# SW6208_A_A_B_C_L_MCU_188.net
KiCad netlist of a schematic drawn in Altium Designer
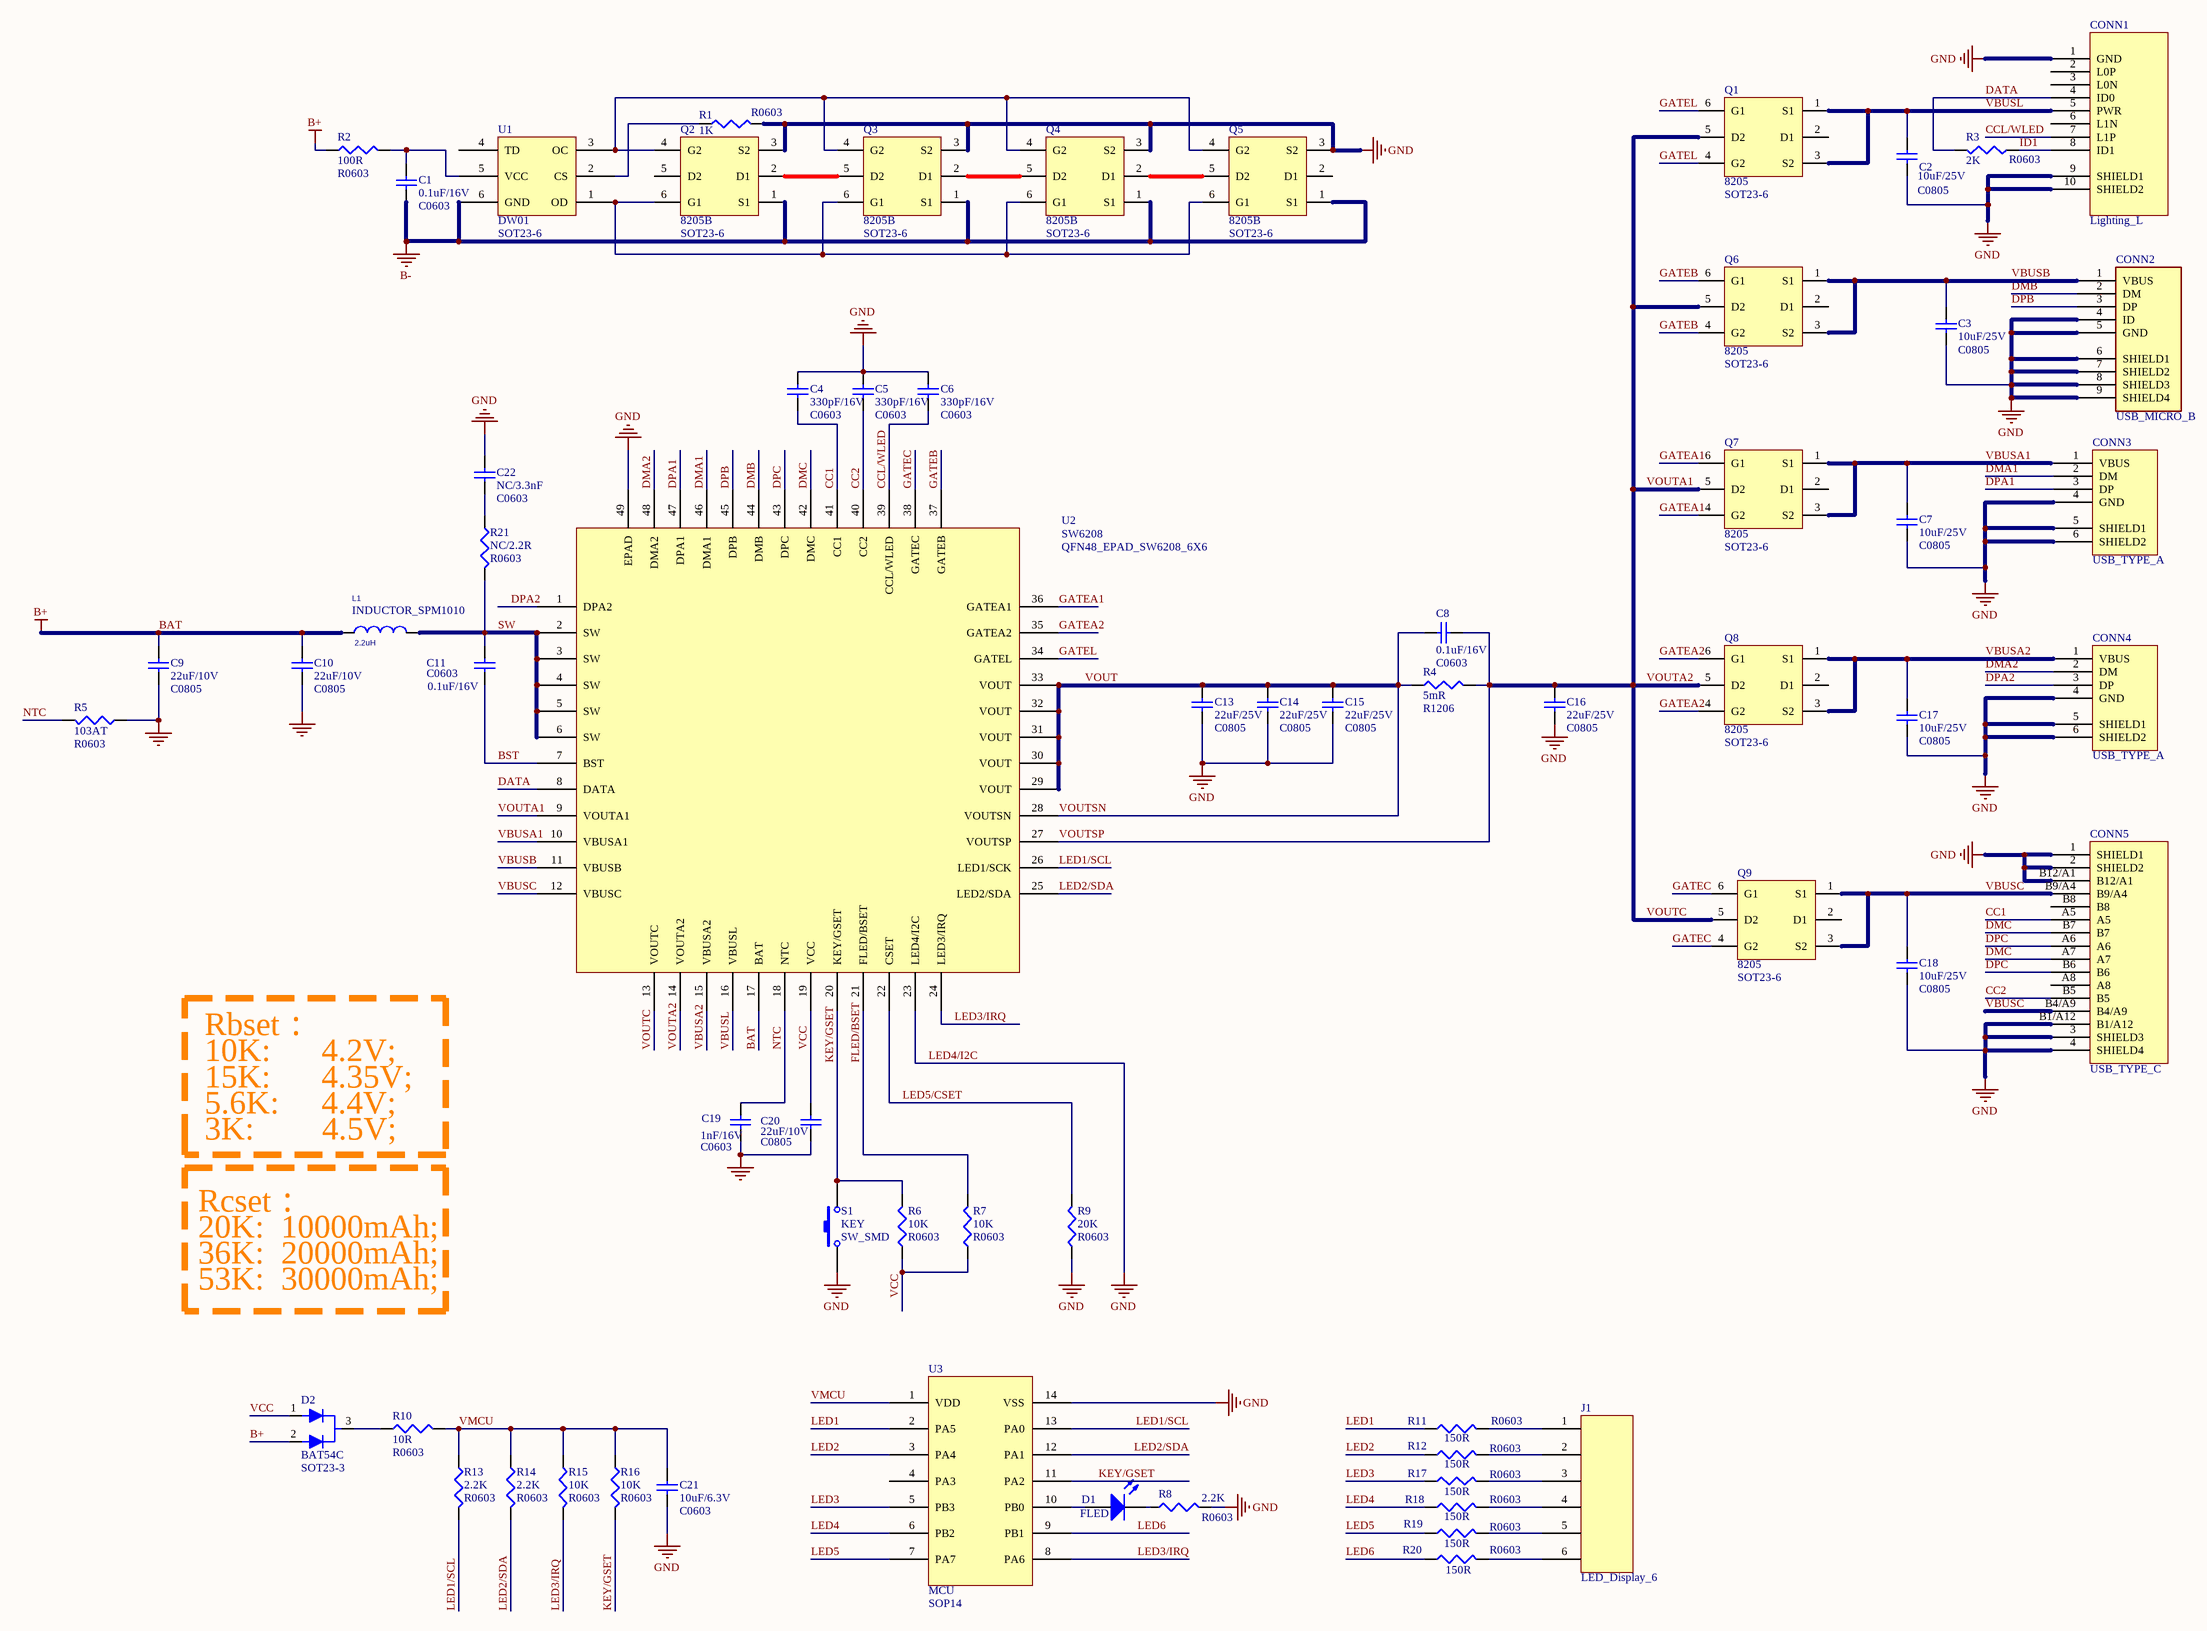
[diagram p0: SW6208+A+A+B+C+L+MCU+普通188数码管.SchDoc]

(export (version "E")
  (design (tool "Eeschema 10.0.6"))
  (components
    (comp (ref "C1")
      (value "0.1uF/16V")
      (footprint "C0603")
      (description "Capacitor")
      (fields (field (name "PUBLISHER") "Altium Limited"))
      (libsource (lib "参考设计器件原理图更新") (part "CAP0603"))
    )
    (comp (ref "C2")
      (value "10uF/25V")
      (footprint "C0805")
      (description "Capacitor")
      (fields (field (name "PUBLISHER") "Altium Limited"))
      (libsource (lib "参考设计器件原理图更新") (part "CAP0805"))
    )
    (comp (ref "C3")
      (value "10uF/25V")
      (footprint "C0805")
      (description "Capacitor")
      (fields (field (name "PUBLISHER") "Altium Limited"))
      (libsource (lib "参考设计器件原理图更新") (part "CAP0805"))
    )
    (comp (ref "C4")
      (value "330pF/16V")
      (footprint "C0603")
      (description "Capacitor")
      (fields (field (name "PUBLISHER") "Altium Limited"))
      (libsource (lib "参考设计器件原理图更新") (part "CAP0603"))
    )
    (comp (ref "C5")
      (value "330pF/16V")
      (footprint "C0603")
      (description "Capacitor")
      (fields (field (name "PUBLISHER") "Altium Limited"))
      (libsource (lib "参考设计器件原理图更新") (part "CAP0603"))
    )
    (comp (ref "C6")
      (value "330pF/16V")
      (footprint "C0603")
      (description "Capacitor")
      (fields (field (name "PUBLISHER") "Altium Limited"))
      (libsource (lib "参考设计器件原理图更新") (part "CAP0603"))
    )
    (comp (ref "C7")
      (value "10uF/25V")
      (footprint "C0805")
      (description "Capacitor")
      (fields (field (name "PUBLISHER") "Altium Limited"))
      (libsource (lib "参考设计器件原理图更新") (part "CAP0805"))
    )
    (comp (ref "C8")
      (value "0.1uF/16V")
      (footprint "C0603")
      (description "Capacitor")
      (fields (field (name "PUBLISHER") "Altium Limited"))
      (libsource (lib "参考设计器件原理图更新") (part "CAP0603"))
    )
    (comp (ref "C9")
      (value "22uF/10V")
      (footprint "C0805")
      (description "Capacitor")
      (fields (field (name "PUBLISHER") "Altium Limited"))
      (libsource (lib "参考设计器件原理图更新") (part "CAP0805"))
    )
    (comp (ref "C10")
      (value "22uF/10V")
      (footprint "C0805")
      (description "Capacitor")
      (fields (field (name "PUBLISHER") "Altium Limited"))
      (libsource (lib "参考设计器件原理图更新") (part "CAP0805"))
    )
    (comp (ref "C11")
      (value "0.1uF/16V")
      (footprint "C0603")
      (description "Capacitor")
      (fields (field (name "PUBLISHER") "Altium Limited"))
      (libsource (lib "参考设计器件原理图更新") (part "CAP0603"))
    )
    (comp (ref "C13")
      (value "22uF/25V")
      (footprint "C0805")
      (description "Capacitor")
      (fields (field (name "PUBLISHER") "Altium Limited"))
      (libsource (lib "参考设计器件原理图更新") (part "CAP0805"))
    )
    (comp (ref "C14")
      (value "22uF/25V")
      (footprint "C0805")
      (description "Capacitor")
      (fields (field (name "PUBLISHER") "Altium Limited"))
      (libsource (lib "参考设计器件原理图更新") (part "CAP0805"))
    )
    (comp (ref "C15")
      (value "22uF/25V")
      (footprint "C0805")
      (description "Capacitor")
      (fields (field (name "PUBLISHER") "Altium Limited"))
      (libsource (lib "参考设计器件原理图更新") (part "CAP0805"))
    )
    (comp (ref "C16")
      (value "22uF/25V")
      (footprint "C0805")
      (description "Capacitor")
      (fields (field (name "PUBLISHER") "Altium Limited"))
      (libsource (lib "参考设计器件原理图更新") (part "CAP0805"))
    )
    (comp (ref "C17")
      (value "10uF/25V")
      (footprint "C0805")
      (description "Capacitor")
      (fields (field (name "PUBLISHER") "Altium Limited"))
      (libsource (lib "参考设计器件原理图更新") (part "CAP0805"))
    )
    (comp (ref "C18")
      (value "10uF/25V")
      (footprint "C0805")
      (description "Capacitor")
      (fields (field (name "PUBLISHER") "Altium Limited"))
      (libsource (lib "参考设计器件原理图更新") (part "CAP0805"))
    )
    (comp (ref "C19")
      (value "1nF/16V")
      (footprint "C0603")
      (description "Capacitor")
      (fields (field (name "PUBLISHER") "Altium Limited"))
      (libsource (lib "参考设计器件原理图更新") (part "CAP0603"))
    )
    (comp (ref "C20")
      (value "22uF/10V")
      (footprint "C0805")
      (description "Capacitor")
      (fields (field (name "PUBLISHER") "Altium Limited"))
      (libsource (lib "参考设计器件原理图更新") (part "CAP0805"))
    )
    (comp (ref "C21")
      (value "10uF/6.3V")
      (footprint "C0603")
      (description "Capacitor")
      (fields (field (name "PUBLISHER") "Altium Limited"))
      (libsource (lib "参考设计器件原理图更新") (part "CAP0603"))
    )
    (comp (ref "C22")
      (value "NC/3.3nF")
      (footprint "C0603")
      (description "Capacitor")
      (fields (field (name "PUBLISHER") "Altium Limited"))
      (libsource (lib "参考设计器件原理图更新") (part "CAP0603"))
    )
    (comp (ref "CONN1")
      (value "Lighting_L")
      (footprint "Lighting")
      (libsource (lib "参考设计器件原理图更新") (part "LIGHTING_PORT"))
    )
    (comp (ref "CONN2")
      (value "USB_MICRO_B")
      (footprint "USB_MICRO_B")
      (libsource (lib "参考设计器件原理图更新") (part "USB_MICRO_B"))
    )
    (comp (ref "CONN3")
      (value "USB_TYPE_A")
      (footprint "USB_TYPE_A")
      (libsource (lib "参考设计器件原理图更新") (part "USB_TYPE_A"))
    )
    (comp (ref "CONN4")
      (value "USB_TYPE_A")
      (footprint "USB_TYPE_A")
      (libsource (lib "参考设计器件原理图更新") (part "USB_TYPE_A"))
    )
    (comp (ref "CONN5")
      (value "USB_TYPE_C")
      (footprint "LOUISAD:USB_TYPE_C")
      (libsource (lib "参考设计器件原理图更新") (part "USB_TYPE_C"))
    )
    (comp (ref "D1")
      (value "FLED")
      (footprint "LED0603")
      (description "LED")
      (fields (field (name "PUBLISHER") "Altium Limited"))
      (libsource (lib "参考设计器件原理图更新") (part "LED_0603"))
    )
    (comp (ref "D2")
      (value "BAT54C")
      (footprint "SOT23-3")
      (description "Diode")
      (libsource (lib "参考设计器件原理图更新") (part "BAT54C"))
    )
    (comp (ref "J1")
      (value "LED_Display_6")
      (footprint "SEG-6")
      (description "188_LED_Display")
      (libsource (lib "参考设计器件原理图更新") (part "LED_Display_6"))
    )
    (comp (ref "L1")
      (value "2.2uH")
      (footprint "INDUCTOR_SPM1010")
      (description "INDUCTOR")
      (libsource (lib "参考设计器件原理图更新") (part "INDUCTOR_SPM1010"))
    )
    (comp (ref "Q1")
      (value "8205")
      (footprint "SOT23-6")
      (description "NMOS")
      (fields (field (name "FOOTPRINF") "SOT23-6"))
      (libsource (lib "参考设计器件原理图更新") (part "8205"))
    )
    (comp (ref "Q2")
      (value "8205B")
      (footprint "SOT23-6")
      (description "NMOS")
      (fields (field (name "FOOTPRINF") "SOT23-6"))
      (libsource (lib "") (part "8205_1"))
    )
    (comp (ref "Q3")
      (value "8205B")
      (footprint "SOT23-6")
      (description "NMOS")
      (fields (field (name "FOOTPRINF") "SOT23-6"))
      (libsource (lib "") (part "8205_1"))
    )
    (comp (ref "Q4")
      (value "8205B")
      (footprint "SOT23-6")
      (description "NMOS")
      (fields (field (name "FOOTPRINF") "SOT23-6"))
      (libsource (lib "") (part "8205_1"))
    )
    (comp (ref "Q5")
      (value "8205B")
      (footprint "SOT23-6")
      (description "NMOS")
      (fields (field (name "FOOTPRINF") "SOT23-6"))
      (libsource (lib "") (part "8205_1"))
    )
    (comp (ref "Q6")
      (value "8205")
      (footprint "SOT23-6")
      (description "NMOS")
      (fields (field (name "FOOTPRINF") "SOT23-6"))
      (libsource (lib "参考设计器件原理图更新") (part "8205"))
    )
    (comp (ref "Q7")
      (value "8205")
      (footprint "SOT23-6")
      (description "NMOS")
      (fields (field (name "FOOTPRINF") "SOT23-6"))
      (libsource (lib "参考设计器件原理图更新") (part "8205"))
    )
    (comp (ref "Q8")
      (value "8205")
      (footprint "SOT23-6")
      (description "NMOS")
      (fields (field (name "FOOTPRINF") "SOT23-6"))
      (libsource (lib "参考设计器件原理图更新") (part "8205"))
    )
    (comp (ref "Q9")
      (value "8205")
      (footprint "SOT23-6")
      (description "NMOS")
      (fields (field (name "FOOTPRINF") "SOT23-6"))
      (libsource (lib "参考设计器件原理图更新") (part "8205"))
    )
    (comp (ref "R1")
      (value "1K")
      (footprint "R0603")
      (description "Resistor")
      (fields (field (name "PUBLISHER") "Altium Limited"))
      (libsource (lib "参考设计器件原理图更新") (part "RES_0603"))
    )
    (comp (ref "R2")
      (value "100R")
      (footprint "R0603")
      (description "Resistor")
      (fields (field (name "PUBLISHER") "Altium Limited"))
      (libsource (lib "参考设计器件原理图更新") (part "RES_0603"))
    )
    (comp (ref "R3")
      (value "2K")
      (footprint "R0603")
      (description "Resistor")
      (fields (field (name "PUBLISHER") "Altium Limited"))
      (libsource (lib "参考设计器件原理图更新") (part "RES_0603"))
    )
    (comp (ref "R4")
      (value "5mR")
      (footprint "R1206")
      (description "Resistor")
      (fields (field (name "PUBLISHER") "Altium Limited"))
      (libsource (lib "参考设计器件原理图更新") (part "RES_1206"))
    )
    (comp (ref "R5")
      (value "103AT")
      (footprint "R0603")
      (description "Resistor")
      (fields (field (name "PUBLISHER") "Altium Limited"))
      (libsource (lib "参考设计器件原理图更新") (part "RES_0603"))
    )
    (comp (ref "R6")
      (value "10K")
      (footprint "R0603")
      (description "Resistor")
      (fields (field (name "PUBLISHER") "Altium Limited"))
      (libsource (lib "参考设计器件原理图更新") (part "RES_0603"))
    )
    (comp (ref "R7")
      (value "10K")
      (footprint "R0603")
      (description "Resistor")
      (fields (field (name "PUBLISHER") "Altium Limited"))
      (libsource (lib "参考设计器件原理图更新") (part "RES_0603"))
    )
    (comp (ref "R8")
      (value "2.2K")
      (footprint "R0603")
      (description "Resistor")
      (fields (field (name "PUBLISHER") "Altium Limited"))
      (libsource (lib "参考设计器件原理图更新") (part "RES_0603"))
    )
    (comp (ref "R9")
      (value "20K")
      (footprint "R0603")
      (description "Resistor")
      (fields (field (name "PUBLISHER") "Altium Limited"))
      (libsource (lib "参考设计器件原理图更新") (part "RES_0603"))
    )
    (comp (ref "R10")
      (value "10R")
      (footprint "R0603")
      (description "Resistor")
      (fields (field (name "PUBLISHER") "Altium Limited"))
      (libsource (lib "参考设计器件原理图更新") (part "RES_0603"))
    )
    (comp (ref "R11")
      (value "150R")
      (footprint "R0603")
      (description "Resistor")
      (fields (field (name "PUBLISHER") "Altium Limited"))
      (libsource (lib "参考设计器件原理图更新") (part "RES_0603"))
    )
    (comp (ref "R12")
      (value "150R")
      (footprint "R0603")
      (description "Resistor")
      (fields (field (name "PUBLISHER") "Altium Limited"))
      (libsource (lib "参考设计器件原理图更新") (part "RES_0603"))
    )
    (comp (ref "R13")
      (value "2.2K")
      (footprint "R0603")
      (description "Resistor")
      (fields (field (name "PUBLISHER") "Altium Limited"))
      (libsource (lib "参考设计器件原理图更新") (part "RES_0603"))
    )
    (comp (ref "R14")
      (value "2.2K")
      (footprint "R0603")
      (description "Resistor")
      (fields (field (name "PUBLISHER") "Altium Limited"))
      (libsource (lib "参考设计器件原理图更新") (part "RES_0603"))
    )
    (comp (ref "R15")
      (value "10K")
      (footprint "R0603")
      (description "Resistor")
      (fields (field (name "PUBLISHER") "Altium Limited"))
      (libsource (lib "参考设计器件原理图更新") (part "RES_0603"))
    )
    (comp (ref "R16")
      (value "10K")
      (footprint "R0603")
      (description "Resistor")
      (fields (field (name "PUBLISHER") "Altium Limited"))
      (libsource (lib "参考设计器件原理图更新") (part "RES_0603"))
    )
    (comp (ref "R17")
      (value "150R")
      (footprint "R0603")
      (description "Resistor")
      (fields (field (name "PUBLISHER") "Altium Limited"))
      (libsource (lib "参考设计器件原理图更新") (part "RES_0603"))
    )
    (comp (ref "R18")
      (value "150R")
      (footprint "R0603")
      (description "Resistor")
      (fields (field (name "PUBLISHER") "Altium Limited"))
      (libsource (lib "参考设计器件原理图更新") (part "RES_0603"))
    )
    (comp (ref "R19")
      (value "150R")
      (footprint "R0603")
      (description "Resistor")
      (fields (field (name "PUBLISHER") "Altium Limited"))
      (libsource (lib "参考设计器件原理图更新") (part "RES_0603"))
    )
    (comp (ref "R20")
      (value "150R")
      (footprint "R0603")
      (description "Resistor")
      (fields (field (name "PUBLISHER") "Altium Limited"))
      (libsource (lib "参考设计器件原理图更新") (part "RES_0603"))
    )
    (comp (ref "R21")
      (value "NC/2.2R")
      (footprint "R0603")
      (description "Resistor")
      (fields (field (name "PUBLISHER") "Altium Limited"))
      (libsource (lib "参考设计器件原理图更新") (part "RES_0603"))
    )
    (comp (ref "S1")
      (value "KEY")
      (footprint "SW_SMD")
      (fields (field (name "FOOTPRINF") "SW_SMD"))
      (libsource (lib "参考设计器件原理图更新") (part "SW K"))
    )
    (comp (ref "U1")
      (value "DW01")
      (footprint "SOT23-6")
      (description "BAT_PROTECT_IC")
      (libsource (lib "参考设计器件原理图更新") (part "DW01"))
    )
    (comp (ref "U2")
      (value "SW6208")
      (footprint "QFN48_EPAD_SW6208_6X6")
      (description "IC")
      (libsource (lib "芯片型号原理图") (part "SW6208"))
    )
    (comp (ref "U3")
      (value "MCU")
      (footprint "SOP14")
      (description "IC")
      (libsource (lib "参考设计器件原理图更新") (part "MCU_SOP14"))
    )
  )
  (nets
    (net (code "1") (name "/BST") (class "Default")
      (node (ref "C11") (pin "1") (pinfunction "1_1") (pintype "passive"))
      (node (ref "U2") (pin "7") (pinfunction "BST_7") (pintype "passive"))
    )
    (net (code "2") (name "/CC1") (class "Default")
      (node (ref "C4") (pin "1") (pinfunction "1_1") (pintype "passive"))
      (node (ref "CONN5") (pin "A5") (pinfunction "A5_A5") (pintype "passive"))
      (node (ref "U2") (pin "41") (pinfunction "CC1_41") (pintype "passive"))
    )
    (net (code "3") (name "/CC2") (class "Default")
      (node (ref "C5") (pin "1") (pinfunction "1_1") (pintype "passive"))
      (node (ref "CONN5") (pin "B5") (pinfunction "B5_B5") (pintype "passive"))
      (node (ref "U2") (pin "40") (pinfunction "CC2_40") (pintype "passive"))
    )
    (net (code "4") (name "/CCL{slash}WLED") (class "Default")
      (node (ref "C6") (pin "1") (pinfunction "1_1") (pintype "passive"))
      (node (ref "CONN1") (pin "7") (pinfunction "L1P_7") (pintype "passive"))
      (node (ref "U2") (pin "39") (pinfunction "CCL/WLED_39") (pintype "passive"))
    )
    (net (code "5") (name "/DATA") (class "Default")
      (node (ref "CONN1") (pin "4") (pinfunction "ID0_4") (pintype "passive"))
      (node (ref "R3") (pin "2") (pinfunction "2_2") (pintype "passive"))
      (node (ref "U2") (pin "8") (pinfunction "DATA_8") (pintype "passive"))
    )
    (net (code "6") (name "/DMA1") (class "Default")
      (node (ref "CONN3") (pin "2") (pinfunction "DM_2") (pintype "passive"))
      (node (ref "U2") (pin "46") (pinfunction "DMA1_46") (pintype "passive"))
    )
    (net (code "7") (name "/DMA2") (class "Default")
      (node (ref "CONN4") (pin "2") (pinfunction "DM_2") (pintype "passive"))
      (node (ref "U2") (pin "48") (pinfunction "DMA2_48") (pintype "passive"))
    )
    (net (code "8") (name "/DMB") (class "Default")
      (node (ref "CONN2") (pin "2") (pinfunction "DM_2") (pintype "passive"))
      (node (ref "U2") (pin "44") (pinfunction "DMB_44") (pintype "passive"))
    )
    (net (code "9") (name "/DMC") (class "Default")
      (node (ref "CONN5") (pin "A7") (pinfunction "A7_A7") (pintype "passive"))
      (node (ref "CONN5") (pin "B7") (pinfunction "B7_B7") (pintype "passive"))
      (node (ref "U2") (pin "42") (pinfunction "DMC_42") (pintype "passive"))
    )
    (net (code "10") (name "/DPA1") (class "Default")
      (node (ref "CONN3") (pin "3") (pinfunction "DP_3") (pintype "passive"))
      (node (ref "U2") (pin "47") (pinfunction "DPA1_47") (pintype "passive"))
    )
    (net (code "11") (name "/DPA2") (class "Default")
      (node (ref "CONN4") (pin "3") (pinfunction "DP_3") (pintype "passive"))
      (node (ref "U2") (pin "1") (pinfunction "DPA2_1") (pintype "passive"))
    )
    (net (code "12") (name "/DPB") (class "Default")
      (node (ref "CONN2") (pin "3") (pinfunction "DP_3") (pintype "passive"))
      (node (ref "U2") (pin "45") (pinfunction "DPB_45") (pintype "passive"))
    )
    (net (code "13") (name "/DPC") (class "Default")
      (node (ref "CONN5") (pin "A6") (pinfunction "A6_A6") (pintype "passive"))
      (node (ref "CONN5") (pin "B6") (pinfunction "B6_B6") (pintype "passive"))
      (node (ref "U2") (pin "43") (pinfunction "DPC_43") (pintype "passive"))
    )
    (net (code "14") (name "/FLED{slash}BSET") (class "Default")
      (node (ref "R7") (pin "2") (pinfunction "2_2") (pintype "passive"))
      (node (ref "U2") (pin "21") (pinfunction "FLED/BSET_21") (pintype "passive"))
    )
    (net (code "15") (name "/GATEA1") (class "Default")
      (node (ref "Q7") (pin "4") (pinfunction "G2_4") (pintype "passive"))
      (node (ref "Q7") (pin "6") (pinfunction "G1_6") (pintype "passive"))
      (node (ref "U2") (pin "36") (pinfunction "GATEA1_36") (pintype "passive"))
    )
    (net (code "16") (name "/GATEA2") (class "Default")
      (node (ref "Q8") (pin "4") (pinfunction "G2_4") (pintype "passive"))
      (node (ref "Q8") (pin "6") (pinfunction "G1_6") (pintype "passive"))
      (node (ref "U2") (pin "35") (pinfunction "GATEA2_35") (pintype "passive"))
    )
    (net (code "17") (name "/GATEB") (class "Default")
      (node (ref "Q6") (pin "4") (pinfunction "G2_4") (pintype "passive"))
      (node (ref "Q6") (pin "6") (pinfunction "G1_6") (pintype "passive"))
      (node (ref "U2") (pin "37") (pinfunction "GATEB_37") (pintype "passive"))
    )
    (net (code "18") (name "/GATEC") (class "Default")
      (node (ref "Q9") (pin "4") (pinfunction "G2_4") (pintype "passive"))
      (node (ref "Q9") (pin "6") (pinfunction "G1_6") (pintype "passive"))
      (node (ref "U2") (pin "38") (pinfunction "GATEC_38") (pintype "passive"))
    )
    (net (code "19") (name "/GATEL") (class "Default")
      (node (ref "Q1") (pin "4") (pinfunction "G2_4") (pintype "passive"))
      (node (ref "Q1") (pin "6") (pinfunction "G1_6") (pintype "passive"))
      (node (ref "U2") (pin "34") (pinfunction "GATEL_34") (pintype "passive"))
    )
    (net (code "20") (name "/ID1") (class "Default")
      (node (ref "CONN1") (pin "8") (pinfunction "ID1_8") (pintype "passive"))
      (node (ref "R3") (pin "1") (pinfunction "1_1") (pintype "passive"))
    )
    (net (code "21") (name "/KEY{slash}GSET") (class "Default")
      (node (ref "R16") (pin "2") (pinfunction "2_2") (pintype "passive"))
      (node (ref "R6") (pin "2") (pinfunction "2_2") (pintype "passive"))
      (node (ref "S1") (pin "2") (pinfunction "2_2") (pintype "passive"))
      (node (ref "U2") (pin "20") (pinfunction "KEY/GSET_20") (pintype "passive"))
      (node (ref "U3") (pin "11") (pinfunction "PA2_11") (pintype "passive"))
    )
    (net (code "22") (name "/LED1") (class "Default")
      (node (ref "R11") (pin "1") (pinfunction "1_1") (pintype "passive"))
      (node (ref "U3") (pin "2") (pinfunction "PA5_2") (pintype "passive"))
    )
    (net (code "23") (name "/LED1{slash}SCL") (class "Default")
      (node (ref "R13") (pin "2") (pinfunction "2_2") (pintype "passive"))
      (node (ref "U2") (pin "26") (pinfunction "LED1/SCK_26") (pintype "passive"))
      (node (ref "U3") (pin "13") (pinfunction "PA0_13") (pintype "passive"))
    )
    (net (code "24") (name "/LED2") (class "Default")
      (node (ref "R12") (pin "1") (pinfunction "1_1") (pintype "passive"))
      (node (ref "U3") (pin "3") (pinfunction "PA4_3") (pintype "passive"))
    )
    (net (code "25") (name "/LED2{slash}SDA") (class "Default")
      (node (ref "R14") (pin "2") (pinfunction "2_2") (pintype "passive"))
      (node (ref "U2") (pin "25") (pinfunction "LED2/SDA_25") (pintype "passive"))
      (node (ref "U3") (pin "12") (pinfunction "PA1_12") (pintype "passive"))
    )
    (net (code "26") (name "/LED3") (class "Default")
      (node (ref "R17") (pin "1") (pinfunction "1_1") (pintype "passive"))
      (node (ref "U3") (pin "5") (pinfunction "PB3_5") (pintype "passive"))
    )
    (net (code "27") (name "/LED3{slash}IRQ") (class "Default")
      (node (ref "R15") (pin "2") (pinfunction "2_2") (pintype "passive"))
      (node (ref "U2") (pin "24") (pinfunction "LED3/IRQ_24") (pintype "passive"))
      (node (ref "U3") (pin "8") (pinfunction "PA6_8") (pintype "passive"))
    )
    (net (code "28") (name "/LED4") (class "Default")
      (node (ref "R18") (pin "1") (pinfunction "1_1") (pintype "passive"))
      (node (ref "U3") (pin "6") (pinfunction "PB2_6") (pintype "passive"))
    )
    (net (code "29") (name "/LED5") (class "Default")
      (node (ref "R19") (pin "1") (pinfunction "1_1") (pintype "passive"))
      (node (ref "U3") (pin "7") (pinfunction "PA7_7") (pintype "passive"))
    )
    (net (code "30") (name "/LED5{slash}CSET") (class "Default")
      (node (ref "R9") (pin "2") (pinfunction "2_2") (pintype "passive"))
      (node (ref "U2") (pin "22") (pinfunction "CSET_22") (pintype "passive"))
    )
    (net (code "31") (name "/LED6") (class "Default")
      (node (ref "R20") (pin "1") (pinfunction "1_1") (pintype "passive"))
      (node (ref "U3") (pin "9") (pinfunction "PB1_9") (pintype "passive"))
    )
    (net (code "32") (name "/NTC") (class "Default")
      (node (ref "C19") (pin "1") (pinfunction "1_1") (pintype "passive"))
      (node (ref "R5") (pin "2") (pinfunction "2_2") (pintype "passive"))
      (node (ref "U2") (pin "18") (pinfunction "NTC_18") (pintype "passive"))
    )
    (net (code "33") (name "/SW") (class "Default")
      (node (ref "C11") (pin "2") (pinfunction "2_2") (pintype "passive"))
      (node (ref "L1") (pin "2") (pinfunction "2_2") (pintype "passive"))
      (node (ref "R21") (pin "2") (pinfunction "2_2") (pintype "passive"))
      (node (ref "U2") (pin "2") (pinfunction "SW_2") (pintype "passive"))
      (node (ref "U2") (pin "3") (pinfunction "SW_3") (pintype "passive"))
      (node (ref "U2") (pin "4") (pinfunction "SW_4") (pintype "passive"))
      (node (ref "U2") (pin "5") (pinfunction "SW_5") (pintype "passive"))
      (node (ref "U2") (pin "6") (pinfunction "SW_6") (pintype "passive"))
    )
    (net (code "34") (name "/VBUSA1") (class "Default")
      (node (ref "C7") (pin "2") (pinfunction "2_2") (pintype "passive"))
      (node (ref "CONN3") (pin "1") (pinfunction "VBUS_1") (pintype "passive"))
      (node (ref "Q7") (pin "1") (pinfunction "S1_1") (pintype "passive"))
      (node (ref "Q7") (pin "3") (pinfunction "S2_3") (pintype "passive"))
      (node (ref "U2") (pin "10") (pinfunction "VBUSA1_10") (pintype "passive"))
    )
    (net (code "35") (name "/VBUSA2") (class "Default")
      (node (ref "C17") (pin "2") (pinfunction "2_2") (pintype "passive"))
      (node (ref "CONN4") (pin "1") (pinfunction "VBUS_1") (pintype "passive"))
      (node (ref "Q8") (pin "1") (pinfunction "S1_1") (pintype "passive"))
      (node (ref "Q8") (pin "3") (pinfunction "S2_3") (pintype "passive"))
      (node (ref "U2") (pin "15") (pinfunction "VBUSA2_15") (pintype "passive"))
    )
    (net (code "36") (name "/VBUSB") (class "Default")
      (node (ref "C3") (pin "2") (pinfunction "2_2") (pintype "passive"))
      (node (ref "CONN2") (pin "1") (pinfunction "VBUS_1") (pintype "passive"))
      (node (ref "Q6") (pin "1") (pinfunction "S1_1") (pintype "passive"))
      (node (ref "Q6") (pin "3") (pinfunction "S2_3") (pintype "passive"))
      (node (ref "U2") (pin "11") (pinfunction "VBUSB_11") (pintype "passive"))
    )
    (net (code "37") (name "/VBUSC") (class "Default")
      (node (ref "C18") (pin "2") (pinfunction "2_2") (pintype "passive"))
      (node (ref "CONN5") (pin "B4/A9") (pinfunction "B4/A9_B4/A9") (pintype "passive"))
      (node (ref "CONN5") (pin "B9/A4") (pinfunction "B9/A4_B9/A4") (pintype "passive"))
      (node (ref "Q9") (pin "1") (pinfunction "S1_1") (pintype "passive"))
      (node (ref "Q9") (pin "3") (pinfunction "S2_3") (pintype "passive"))
      (node (ref "U2") (pin "12") (pinfunction "VBUSC_12") (pintype "passive"))
    )
    (net (code "38") (name "/VBUSL") (class "Default")
      (node (ref "C2") (pin "2") (pinfunction "2_2") (pintype "passive"))
      (node (ref "CONN1") (pin "5") (pinfunction "PWR_5") (pintype "passive"))
      (node (ref "Q1") (pin "1") (pinfunction "S1_1") (pintype "passive"))
      (node (ref "Q1") (pin "3") (pinfunction "S2_3") (pintype "passive"))
      (node (ref "U2") (pin "16") (pinfunction "VBUSL_16") (pintype "passive"))
    )
    (net (code "39") (name "/VCC") (class "Default")
      (node (ref "C20") (pin "1") (pinfunction "1_1") (pintype "passive"))
      (node (ref "D2") (pin "1") (pintype "passive"))
      (node (ref "R6") (pin "1") (pinfunction "1_1") (pintype "passive"))
      (node (ref "R7") (pin "1") (pinfunction "1_1") (pintype "passive"))
      (node (ref "U2") (pin "19") (pinfunction "VCC_19") (pintype "passive"))
    )
    (net (code "40") (name "/VMCU") (class "Default")
      (node (ref "C21") (pin "2") (pinfunction "2_2") (pintype "passive"))
      (node (ref "R10") (pin "2") (pinfunction "2_2") (pintype "passive"))
      (node (ref "R13") (pin "1") (pinfunction "1_1") (pintype "passive"))
      (node (ref "R14") (pin "1") (pinfunction "1_1") (pintype "passive"))
      (node (ref "R15") (pin "1") (pinfunction "1_1") (pintype "passive"))
      (node (ref "R16") (pin "1") (pinfunction "1_1") (pintype "passive"))
      (node (ref "U3") (pin "1") (pinfunction "VDD_1") (pintype "passive"))
    )
    (net (code "41") (name "/VOUT") (class "Default")
      (node (ref "C13") (pin "2") (pinfunction "2_2") (pintype "passive"))
      (node (ref "C14") (pin "2") (pinfunction "2_2") (pintype "passive"))
      (node (ref "C15") (pin "2") (pinfunction "2_2") (pintype "passive"))
      (node (ref "C8") (pin "1") (pinfunction "1_1") (pintype "passive"))
      (node (ref "R4") (pin "1") (pinfunction "1_1") (pintype "passive"))
      (node (ref "U2") (pin "28") (pinfunction "VOUTSN_28") (pintype "passive"))
      (node (ref "U2") (pin "29") (pinfunction "VOUT_29") (pintype "passive"))
      (node (ref "U2") (pin "30") (pinfunction "VOUT_30") (pintype "passive"))
      (node (ref "U2") (pin "31") (pinfunction "VOUT_31") (pintype "passive"))
      (node (ref "U2") (pin "32") (pinfunction "VOUT_32") (pintype "passive"))
      (node (ref "U2") (pin "33") (pinfunction "VOUT_33") (pintype "passive"))
    )
    (net (code "42") (name "/VOUTA1") (class "Default")
      (node (ref "C16") (pin "2") (pinfunction "2_2") (pintype "passive"))
      (node (ref "C8") (pin "2") (pinfunction "2_2") (pintype "passive"))
      (node (ref "Q1") (pin "5") (pinfunction "D2_5") (pintype "passive"))
      (node (ref "Q6") (pin "5") (pinfunction "D2_5") (pintype "passive"))
      (node (ref "Q7") (pin "5") (pinfunction "D2_5") (pintype "passive"))
      (node (ref "Q8") (pin "5") (pinfunction "D2_5") (pintype "passive"))
      (node (ref "Q9") (pin "5") (pinfunction "D2_5") (pintype "passive"))
      (node (ref "R4") (pin "2") (pinfunction "2_2") (pintype "passive"))
      (node (ref "U2") (pin "13") (pinfunction "VOUTC_13") (pintype "passive"))
      (node (ref "U2") (pin "14") (pinfunction "VOUTA2_14") (pintype "passive"))
      (node (ref "U2") (pin "27") (pinfunction "VOUTSP_27") (pintype "passive"))
      (node (ref "U2") (pin "9") (pinfunction "VOUTA1_9") (pintype "passive"))
    )
    (net (code "43") (name "B+") (class "Default")
      (node (ref "C10") (pin "2") (pinfunction "2_2") (pintype "passive"))
      (node (ref "C9") (pin "2") (pinfunction "2_2") (pintype "passive"))
      (node (ref "D2") (pin "2") (pintype "passive"))
      (node (ref "L1") (pin "1") (pinfunction "1_1") (pintype "passive"))
      (node (ref "R2") (pin "1") (pinfunction "1_1") (pintype "passive"))
      (node (ref "U2") (pin "17") (pinfunction "BAT_17") (pintype "passive"))
    )
    (net (code "44") (name "B-") (class "Default")
      (node (ref "C1") (pin "1") (pinfunction "1_1") (pintype "passive"))
      (node (ref "Q2") (pin "1") (pinfunction "S1_1") (pintype "passive"))
      (node (ref "Q3") (pin "1") (pinfunction "S1_1") (pintype "passive"))
      (node (ref "Q4") (pin "1") (pinfunction "S1_1") (pintype "passive"))
      (node (ref "Q5") (pin "1") (pinfunction "S1_1") (pintype "passive"))
      (node (ref "U1") (pin "6") (pinfunction "GND_6") (pintype "passive"))
    )
    (net (code "45") (name "GND") (class "Default")
      (node (ref "C10") (pin "1") (pinfunction "1_1") (pintype "passive"))
      (node (ref "C13") (pin "1") (pinfunction "1_1") (pintype "passive"))
      (node (ref "C14") (pin "1") (pinfunction "1_1") (pintype "passive"))
      (node (ref "C15") (pin "1") (pinfunction "1_1") (pintype "passive"))
      (node (ref "C16") (pin "1") (pinfunction "1_1") (pintype "passive"))
      (node (ref "C17") (pin "1") (pinfunction "1_1") (pintype "passive"))
      (node (ref "C18") (pin "1") (pinfunction "1_1") (pintype "passive"))
      (node (ref "C19") (pin "2") (pinfunction "2_2") (pintype "passive"))
      (node (ref "C2") (pin "1") (pinfunction "1_1") (pintype "passive"))
      (node (ref "C20") (pin "2") (pinfunction "2_2") (pintype "passive"))
      (node (ref "C21") (pin "1") (pinfunction "1_1") (pintype "passive"))
      (node (ref "C22") (pin "2") (pinfunction "2_2") (pintype "passive"))
      (node (ref "C3") (pin "1") (pinfunction "1_1") (pintype "passive"))
      (node (ref "C4") (pin "2") (pinfunction "2_2") (pintype "passive"))
      (node (ref "C5") (pin "2") (pinfunction "2_2") (pintype "passive"))
      (node (ref "C6") (pin "2") (pinfunction "2_2") (pintype "passive"))
      (node (ref "C7") (pin "1") (pinfunction "1_1") (pintype "passive"))
      (node (ref "C9") (pin "1") (pinfunction "1_1") (pintype "passive"))
      (node (ref "CONN1") (pin "1") (pinfunction "GND_1") (pintype "passive"))
      (node (ref "CONN1") (pin "10") (pinfunction "SHIELD2_10") (pintype "passive"))
      (node (ref "CONN1") (pin "9") (pinfunction "SHIELD1_9") (pintype "passive"))
      (node (ref "CONN2") (pin "4") (pinfunction "ID_4") (pintype "passive"))
      (node (ref "CONN2") (pin "5") (pinfunction "GND_5") (pintype "passive"))
      (node (ref "CONN2") (pin "6") (pinfunction "SHIELD1_6") (pintype "passive"))
      (node (ref "CONN2") (pin "7") (pinfunction "SHIELD2_7") (pintype "passive"))
      (node (ref "CONN2") (pin "8") (pinfunction "SHIELD3_8") (pintype "passive"))
      (node (ref "CONN2") (pin "9") (pinfunction "SHIELD4_9") (pintype "passive"))
      (node (ref "CONN3") (pin "4") (pinfunction "GND_4") (pintype "passive"))
      (node (ref "CONN3") (pin "5") (pinfunction "SHIELD1_5") (pintype "passive"))
      (node (ref "CONN3") (pin "6") (pinfunction "SHIELD2_6") (pintype "passive"))
      (node (ref "CONN4") (pin "4") (pinfunction "GND_4") (pintype "passive"))
      (node (ref "CONN4") (pin "5") (pinfunction "SHIELD1_5") (pintype "passive"))
      (node (ref "CONN4") (pin "6") (pinfunction "SHIELD2_6") (pintype "passive"))
      (node (ref "CONN5") (pin "1") (pinfunction "SHIELD1_1") (pintype "passive"))
      (node (ref "CONN5") (pin "2") (pinfunction "SHIELD2_2") (pintype "passive"))
      (node (ref "CONN5") (pin "3") (pinfunction "SHIELD3_3") (pintype "passive"))
      (node (ref "CONN5") (pin "4") (pinfunction "SHIELD4_4") (pintype "passive"))
      (node (ref "CONN5") (pin "B1/A12") (pinfunction "B1/A12_B1/A12") (pintype "passive"))
      (node (ref "CONN5") (pin "B12/A1") (pinfunction "B12/A1_B12/A1") (pintype "passive"))
      (node (ref "Q2") (pin "3") (pinfunction "S2_3") (pintype "passive"))
      (node (ref "Q3") (pin "3") (pinfunction "S2_3") (pintype "passive"))
      (node (ref "Q4") (pin "3") (pinfunction "S2_3") (pintype "passive"))
      (node (ref "Q5") (pin "3") (pinfunction "S2_3") (pintype "passive"))
      (node (ref "R1") (pin "2") (pinfunction "2_2") (pintype "passive"))
      (node (ref "R5") (pin "1") (pinfunction "1_1") (pintype "passive"))
      (node (ref "R8") (pin "2") (pinfunction "2_2") (pintype "passive"))
      (node (ref "R9") (pin "1") (pinfunction "1_1") (pintype "passive"))
      (node (ref "S1") (pin "1") (pinfunction "1_1") (pintype "passive"))
      (node (ref "U2") (pin "23") (pinfunction "LED4/I2C_23") (pintype "passive"))
      (node (ref "U2") (pin "49") (pinfunction "EPAD_49") (pintype "passive"))
      (node (ref "U3") (pin "14") (pinfunction "VSS_14") (pintype "passive"))
    )
    (net (code "46") (name "Net-(C22-Pad1)") (class "Default")
      (node (ref "C22") (pin "1") (pinfunction "1_1") (pintype "passive"))
      (node (ref "R21") (pin "1") (pinfunction "1_1") (pintype "passive"))
    )
    (net (code "47") (name "Net-(D1-A)") (class "Default")
      (node (ref "D1") (pin "1") (pinfunction "A_1") (pintype "passive"))
      (node (ref "U3") (pin "10") (pinfunction "PB0_10") (pintype "passive"))
    )
    (net (code "48") (name "Net-(D1-K)") (class "Default")
      (node (ref "D1") (pin "2") (pinfunction "K_2") (pintype "passive"))
      (node (ref "R8") (pin "1") (pinfunction "1_1") (pintype "passive"))
    )
    (net (code "49") (name "Net-(D2-Pad3)") (class "Default")
      (node (ref "D2") (pin "3") (pintype "passive"))
      (node (ref "R10") (pin "1") (pinfunction "1_1") (pintype "passive"))
    )
    (net (code "50") (name "Net-(J1-Pad1)") (class "Default")
      (node (ref "J1") (pin "1") (pinfunction "1_1") (pintype "passive"))
      (node (ref "R11") (pin "2") (pinfunction "2_2") (pintype "passive"))
    )
    (net (code "51") (name "Net-(J1-Pad2)") (class "Default")
      (node (ref "J1") (pin "2") (pinfunction "2_2") (pintype "passive"))
      (node (ref "R12") (pin "2") (pinfunction "2_2") (pintype "passive"))
    )
    (net (code "52") (name "Net-(J1-Pad3)") (class "Default")
      (node (ref "J1") (pin "3") (pinfunction "3_3") (pintype "passive"))
      (node (ref "R17") (pin "2") (pinfunction "2_2") (pintype "passive"))
    )
    (net (code "53") (name "Net-(J1-Pad4)") (class "Default")
      (node (ref "J1") (pin "4") (pinfunction "4_4") (pintype "passive"))
      (node (ref "R18") (pin "2") (pinfunction "2_2") (pintype "passive"))
    )
    (net (code "54") (name "Net-(J1-Pad5)") (class "Default")
      (node (ref "J1") (pin "5") (pinfunction "5_5") (pintype "passive"))
      (node (ref "R19") (pin "2") (pinfunction "2_2") (pintype "passive"))
    )
    (net (code "55") (name "Net-(J1-Pad6)") (class "Default")
      (node (ref "J1") (pin "6") (pinfunction "6_6") (pintype "passive"))
      (node (ref "R20") (pin "2") (pinfunction "2_2") (pintype "passive"))
    )
    (net (code "56") (name "Net-(Q2-D1)") (class "Default")
      (node (ref "Q2") (pin "2") (pinfunction "D1_2") (pintype "passive"))
      (node (ref "Q3") (pin "5") (pinfunction "D2_5") (pintype "passive"))
    )
    (net (code "57") (name "Net-(Q2-G1)") (class "Default")
      (node (ref "Q2") (pin "6") (pinfunction "G1_6") (pintype "passive"))
      (node (ref "Q3") (pin "6") (pinfunction "G1_6") (pintype "passive"))
      (node (ref "Q4") (pin "6") (pinfunction "G1_6") (pintype "passive"))
      (node (ref "Q5") (pin "6") (pinfunction "G1_6") (pintype "passive"))
      (node (ref "U1") (pin "1") (pinfunction "OD_1") (pintype "passive"))
    )
    (net (code "58") (name "Net-(Q2-G2)") (class "Default")
      (node (ref "Q2") (pin "4") (pinfunction "G2_4") (pintype "passive"))
      (node (ref "Q3") (pin "4") (pinfunction "G2_4") (pintype "passive"))
      (node (ref "Q4") (pin "4") (pinfunction "G2_4") (pintype "passive"))
      (node (ref "Q5") (pin "4") (pinfunction "G2_4") (pintype "passive"))
      (node (ref "U1") (pin "3") (pinfunction "OC_3") (pintype "passive"))
    )
    (net (code "59") (name "Net-(Q3-D1)") (class "Default")
      (node (ref "Q3") (pin "2") (pinfunction "D1_2") (pintype "passive"))
      (node (ref "Q4") (pin "5") (pinfunction "D2_5") (pintype "passive"))
    )
    (net (code "60") (name "Net-(Q4-D1)") (class "Default")
      (node (ref "Q4") (pin "2") (pinfunction "D1_2") (pintype "passive"))
      (node (ref "Q5") (pin "5") (pinfunction "D2_5") (pintype "passive"))
    )
    (net (code "61") (name "Net-(U1-CS)") (class "Default")
      (node (ref "R1") (pin "1") (pinfunction "1_1") (pintype "passive"))
      (node (ref "U1") (pin "2") (pinfunction "CS_2") (pintype "passive"))
    )
    (net (code "62") (name "Net-(U1-VCC)") (class "Default")
      (node (ref "C1") (pin "2") (pinfunction "2_2") (pintype "passive"))
      (node (ref "R2") (pin "2") (pinfunction "2_2") (pintype "passive"))
      (node (ref "U1") (pin "5") (pinfunction "VCC_5") (pintype "passive"))
    )
    (net (code "63") (name "unconnected-(CONN1-L0N-Pad3)") (class "Default")
      (node (ref "CONN1") (pin "3") (pinfunction "L0N_3") (pintype "passive"))
    )
    (net (code "64") (name "unconnected-(CONN1-L0P-Pad2)") (class "Default")
      (node (ref "CONN1") (pin "2") (pinfunction "L0P_2") (pintype "passive"))
    )
    (net (code "65") (name "unconnected-(CONN1-L1N-Pad6)") (class "Default")
      (node (ref "CONN1") (pin "6") (pinfunction "L1N_6") (pintype "passive"))
    )
    (net (code "66") (name "unconnected-(CONN5-PadA8)") (class "Default")
      (node (ref "CONN5") (pin "A8") (pinfunction "A8_A8") (pintype "passive"))
    )
    (net (code "67") (name "unconnected-(CONN5-PadB8)") (class "Default")
      (node (ref "CONN5") (pin "B8") (pinfunction "B8_B8") (pintype "passive"))
    )
    (net (code "68") (name "unconnected-(Q1-D1-Pad2)") (class "Default")
      (node (ref "Q1") (pin "2") (pinfunction "D1_2") (pintype "passive"))
    )
    (net (code "69") (name "unconnected-(Q2-D2-Pad5)") (class "Default")
      (node (ref "Q2") (pin "5") (pinfunction "D2_5") (pintype "passive"))
    )
    (net (code "70") (name "unconnected-(Q5-D1-Pad2)") (class "Default")
      (node (ref "Q5") (pin "2") (pinfunction "D1_2") (pintype "passive"))
    )
    (net (code "71") (name "unconnected-(Q6-D1-Pad2)") (class "Default")
      (node (ref "Q6") (pin "2") (pinfunction "D1_2") (pintype "passive"))
    )
    (net (code "72") (name "unconnected-(Q7-D1-Pad2)") (class "Default")
      (node (ref "Q7") (pin "2") (pinfunction "D1_2") (pintype "passive"))
    )
    (net (code "73") (name "unconnected-(Q8-D1-Pad2)") (class "Default")
      (node (ref "Q8") (pin "2") (pinfunction "D1_2") (pintype "passive"))
    )
    (net (code "74") (name "unconnected-(Q9-D1-Pad2)") (class "Default")
      (node (ref "Q9") (pin "2") (pinfunction "D1_2") (pintype "passive"))
    )
    (net (code "75") (name "unconnected-(U1-TD-Pad4)") (class "Default")
      (node (ref "U1") (pin "4") (pinfunction "TD_4") (pintype "passive"))
    )
    (net (code "76") (name "unconnected-(U3-PA3-Pad4)") (class "Default")
      (node (ref "U3") (pin "4") (pinfunction "PA3_4") (pintype "passive"))
    )
  )
)
